# design.net
KiCad netlist of a schematic drawn in EAGLE
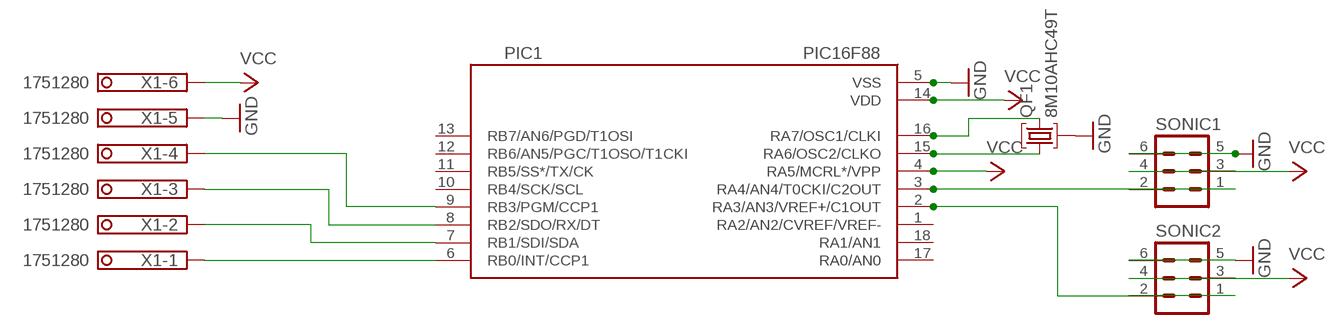
[diagram p0: schematic, sheet 1]

(export (version "E")
  (design (tool "Eeschema 10.0.6"))
  (components
    (comp (ref "PIC1")
      (value "PIC16F88")
      (footprint "eagle-import:DIL18")
      (libsource (lib "eagle-import") (part "PIC16F88"))
    )
    (comp (ref "QF1")
      (value "8M10AHC49T")
      (footprint "eagle-import:HC49U")
      (libsource (lib "eagle-import") (part "8M10AHC49T"))
    )
    (comp (ref "SONIC1")
      (value "ML6")
      (footprint "eagle-import:ML6")
      (libsource (lib "eagle-import") (part "ML6"))
    )
    (comp (ref "SONIC2")
      (value "ML6")
      (footprint "eagle-import:ML6")
      (libsource (lib "eagle-import") (part "ML6"))
    )
    (comp (ref "X1")
      (value "1751280")
      (footprint "eagle-import:1751280")
      (libsource (lib "eagle-import") (part "1751280"))
    )
  )
  (nets
    (net (code "1") (name "GND") (class "Default")
      (node (ref "PIC1") (pin "5") (pinfunction "VSS_5") (pintype "bidirectional"))
      (node (ref "QF1") (pin "2") (pinfunction "2_2") (pintype "passive"))
      (node (ref "SONIC1") (pin "5") (pinfunction "5_5") (pintype "passive"))
      (node (ref "SONIC1") (pin "6") (pinfunction "6_6") (pintype "passive"))
      (node (ref "SONIC2") (pin "5") (pinfunction "5_5") (pintype "passive"))
      (node (ref "SONIC2") (pin "6") (pinfunction "6_6") (pintype "passive"))
      (node (ref "X1") (pin "5") (pinfunction "K_5") (pintype "passive"))
    )
    (net (code "2") (name "Net-(PIC1-RA3{slash}AN3{slash}VREF+{slash}C1OUT)") (class "Default")
      (node (ref "PIC1") (pin "2") (pinfunction "RA3/AN3/VREF+/C1OUT_2") (pintype "bidirectional"))
      (node (ref "SONIC2") (pin "1") (pinfunction "1_1") (pintype "passive"))
      (node (ref "SONIC2") (pin "2") (pinfunction "2_2") (pintype "passive"))
    )
    (net (code "3") (name "Net-(PIC1-RA4{slash}AN4{slash}T0CKI{slash}C2OUT)") (class "Default")
      (node (ref "PIC1") (pin "3") (pinfunction "RA4/AN4/T0CKI/C2OUT_3") (pintype "bidirectional"))
      (node (ref "SONIC1") (pin "1") (pinfunction "1_1") (pintype "passive"))
      (node (ref "SONIC1") (pin "2") (pinfunction "2_2") (pintype "passive"))
    )
    (net (code "4") (name "Net-(PIC1-RA6{slash}OSC2{slash}CLKO)") (class "Default")
      (node (ref "PIC1") (pin "15") (pinfunction "RA6/OSC2/CLKO_15") (pintype "bidirectional"))
      (node (ref "QF1") (pin "1") (pinfunction "1_1") (pintype "passive"))
    )
    (net (code "5") (name "Net-(PIC1-RA7{slash}OSC1{slash}CLKI)") (class "Default")
      (node (ref "PIC1") (pin "16") (pinfunction "RA7/OSC1/CLKI_16") (pintype "bidirectional"))
      (node (ref "QF1") (pin "3") (pinfunction "3_3") (pintype "passive"))
    )
    (net (code "6") (name "Net-(PIC1-RB0{slash}INT{slash}CCP1)") (class "Default")
      (node (ref "PIC1") (pin "6") (pinfunction "RB0/INT/CCP1_6") (pintype "bidirectional"))
      (node (ref "X1") (pin "1") (pinfunction "K_1") (pintype "passive"))
    )
    (net (code "7") (name "Net-(PIC1-RB1{slash}SDI{slash}SDA)") (class "Default")
      (node (ref "PIC1") (pin "7") (pinfunction "RB1/SDI/SDA_7") (pintype "bidirectional"))
      (node (ref "X1") (pin "2") (pinfunction "K_2") (pintype "passive"))
    )
    (net (code "8") (name "Net-(PIC1-RB2{slash}SDO{slash}RX{slash}DT)") (class "Default")
      (node (ref "PIC1") (pin "8") (pinfunction "RB2/SDO/RX/DT_8") (pintype "bidirectional"))
      (node (ref "X1") (pin "3") (pinfunction "K_3") (pintype "passive"))
    )
    (net (code "9") (name "Net-(PIC1-RB3{slash}PGM{slash}CCP1)") (class "Default")
      (node (ref "PIC1") (pin "9") (pinfunction "RB3/PGM/CCP1_9") (pintype "bidirectional"))
      (node (ref "X1") (pin "4") (pinfunction "K_4") (pintype "passive"))
    )
    (net (code "10") (name "VCC") (class "Default")
      (node (ref "PIC1") (pin "14") (pinfunction "VDD_14") (pintype "bidirectional"))
      (node (ref "PIC1") (pin "4") (pinfunction "RA5/MCRL*/VPP_4") (pintype "bidirectional"))
      (node (ref "SONIC1") (pin "3") (pinfunction "3_3") (pintype "passive"))
      (node (ref "SONIC1") (pin "4") (pinfunction "4_4") (pintype "passive"))
      (node (ref "SONIC2") (pin "3") (pinfunction "3_3") (pintype "passive"))
      (node (ref "SONIC2") (pin "4") (pinfunction "4_4") (pintype "passive"))
      (node (ref "X1") (pin "6") (pinfunction "K_6") (pintype "passive"))
    )
    (net (code "11") (name "unconnected-(PIC1-RA0{slash}AN0-Pad17)") (class "Default")
      (node (ref "PIC1") (pin "17") (pinfunction "RA0/AN0_17") (pintype "bidirectional"))
    )
    (net (code "12") (name "unconnected-(PIC1-RA1{slash}AN1-Pad18)") (class "Default")
      (node (ref "PIC1") (pin "18") (pinfunction "RA1/AN1_18") (pintype "bidirectional"))
    )
    (net (code "13") (name "unconnected-(PIC1-RA2{slash}AN2{slash}CVREF{slash}VREF--Pad1)") (class "Default")
      (node (ref "PIC1") (pin "1") (pinfunction "RA2/AN2/CVREF/VREF-_1") (pintype "bidirectional"))
    )
    (net (code "14") (name "unconnected-(PIC1-RB4{slash}SCK{slash}SCL-Pad10)") (class "Default")
      (node (ref "PIC1") (pin "10") (pinfunction "RB4/SCK/SCL_10") (pintype "bidirectional"))
    )
    (net (code "15") (name "unconnected-(PIC1-RB5{slash}SS*{slash}TX{slash}CK-Pad11)") (class "Default")
      (node (ref "PIC1") (pin "11") (pinfunction "RB5/SS*/TX/CK_11") (pintype "bidirectional"))
    )
    (net (code "16") (name "unconnected-(PIC1-RB6{slash}AN5{slash}PGC{slash}T1OSO{slash}T1CKI-Pad12)") (class "Default")
      (node (ref "PIC1") (pin "12") (pinfunction "RB6/AN5/PGC/T1OSO/T1CKI_12") (pintype "bidirectional"))
    )
    (net (code "17") (name "unconnected-(PIC1-RB7{slash}AN6{slash}PGD{slash}T1OSI-Pad13)") (class "Default")
      (node (ref "PIC1") (pin "13") (pinfunction "RB7/AN6/PGD/T1OSI_13") (pintype "bidirectional"))
    )
  )
)
